# ATmega328P_design.net
KiCad netlist of a schematic drawn in Altium Designer
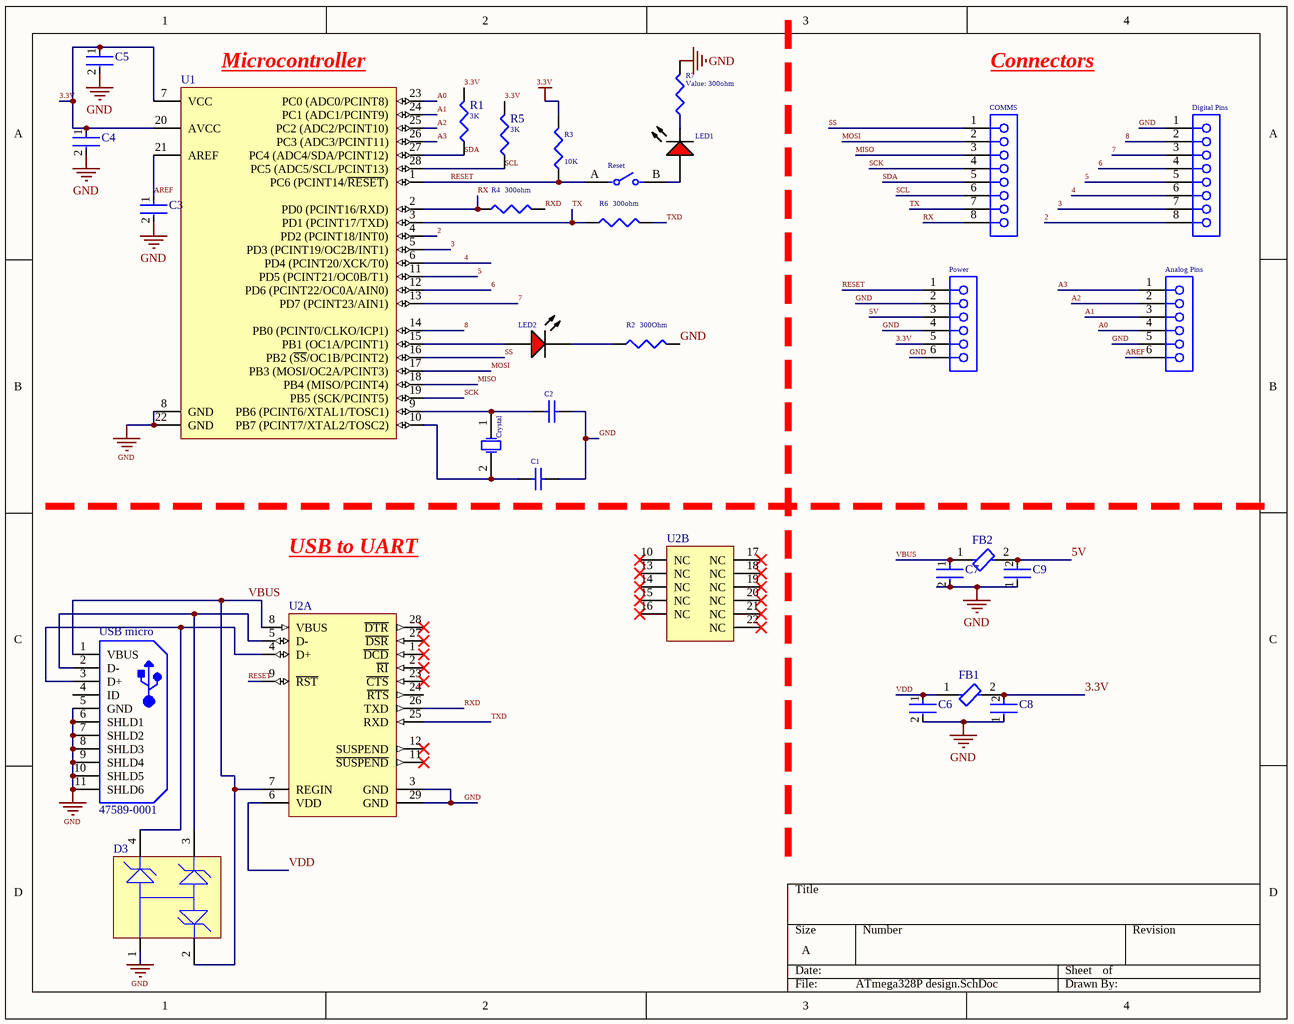
[diagram p0: ATmega328P design.SchDoc]

(export (version "E")
  (design (tool "Eeschema 10.0.6"))
  (components
    (comp (ref "Analog Pins")
      (value "SSW-106-02-G-S")
      (footprint "SMTC-SSW-106-02-X-S")
      (description "SQ Post Socket, Through-hole, Vertical, -55 to 125 degC, 2.54mm Pitch, 6-Pin, Female, RoHS")
      (fields (field (name "MANUFACTURER") "Samtec"))
      (libsource (lib "Altium Content Vault") (part "SMTC-SSW-106-02-X-S-X"))
    )
    (comp (ref "C1")
      (value "22pF")
      (footprint "CAPC1608X90X35LL15T15")
      (fields
        (field (name "MANUFACTURER") "AVX Interconnect / Elco")
        (field (name "PART NUMBER") "06031A220KAT2A")
      )
      (libsource (lib "Altium Content Vault") (part "CAP"))
    )
    (comp (ref "C2")
      (value "22pf")
      (footprint "CAPC1608X90X35LL15T15")
      (fields
        (field (name "MANUFACTURER") "AVX Interconnect / Elco")
        (field (name "PART NUMBER") "06031A220KAT2A")
      )
      (libsource (lib "Altium Content Vault") (part "CAP"))
    )
    (comp (ref "C3")
      (value "GRM188R60J106ME47D")
      (footprint "FP-GRM188-0_1-e0_2_0_55-IPC_A")
      (description "Chip Multilayer Ceramic Capacitors for General Purpose, 0603, 0.1uF, X5R, 15%, 20%, 6.3V")
      (fields (field (name "VOLTAGE") "6.3V") (field (name "TOLERANCE") "20%"))
      (libsource (lib "Altium Content Vault") (part "02cd4be3c70576c341d710602a673aa"))
    )
    (comp (ref "C4")
      (value "GRM188R61A226ME15D")
      (footprint "FP-GRM188-0_2-IPC_C")
      (description "Chip Multilayer Ceramic Capacitors for General Purpose, 0603, 22uF, X5R, 15%, 20%, 10V")
      (fields (field (name "TOLERANCE") "20%"))
      (libsource (lib "Altium Content Vault") (part "11868f565c42a9108669ba33697ecf6"))
    )
    (comp (ref "C5")
      (value "GRM188R61A226ME15D")
      (footprint "FP-GRM188-0_2-IPC_C")
      (description "Chip Multilayer Ceramic Capacitors for General Purpose, 0603, 22uF, X5R, 15%, 20%, 10V")
      (fields (field (name "TOLERANCE") "20%"))
      (libsource (lib "Altium Content Vault") (part "11868f565c42a9108669ba33697ecf6"))
    )
    (comp (ref "C6")
      (value "GRM188R6YA106MA73D")
      (footprint "FP-GRM188-0_2-IPC_C")
      (description "Chip Multilayer Ceramic Capacitors for General Purpose, 0603, 10uF, X5R, 15%, 20%, 35V")
      (fields (field (name "TOLERANCE") "20%"))
      (libsource (lib "Altium Content Vault") (part "11868f565c42a9108669ba33697ecf6"))
    )
    (comp (ref "C7")
      (value "GRM188R6YA106MA73D")
      (footprint "FP-GRM188-0_2-IPC_C")
      (description "Chip Multilayer Ceramic Capacitors for General Purpose, 0603, 10uF, X5R, 15%, 20%, 35V")
      (fields (field (name "TOLERANCE") "20%"))
      (libsource (lib "Altium Content Vault") (part "11868f565c42a9108669ba33697ecf6"))
    )
    (comp (ref "C8")
      (value "GRM188R60J105KA01D")
      (footprint "FP-GRM188-0_1-MFG")
      (description "CAP CER 1UF 6.3V X5R 0603")
      (fields (field (name "TOLERANCE") "10%") (field (name "VOLTAGE") "6.3V"))
      (libsource (lib "Altium Content Vault") (part "236180d848d6139a670b325ea6854c9"))
    )
    (comp (ref "C9")
      (value "GRM188R60J105KA01D")
      (footprint "FP-GRM188-0_1-MFG")
      (description "CAP CER 1UF 6.3V X5R 0603")
      (fields (field (name "TOLERANCE") "10%") (field (name "VOLTAGE") "6.3V"))
      (libsource (lib "Altium Content Vault") (part "236180d848d6139a670b325ea6854c9"))
    )
    (comp (ref "COMMS")
      (value "SSQ-108-01-F-S")
      (footprint "SMTC-SSQ-108-01-X-S")
      (description "SQ Post Socket, Through-hole, Vertical, -55 to 125 degC, 2.54 mm Pitch, 8-Pin, Female, RoHS")
      (fields (field (name "MANUFACTURER") "Samtec"))
      (libsource (lib "Altium Content Vault") (part "SMTC-SSQ-108-X-X-S-X"))
    )
    (comp (ref "Crystal")
      (value "FOXSDLF/160-20")
      (footprint "FOX-FOXSDLF160-20_V")
      (libsource (lib "Altium Content Vault") (part "XTAL_1-2-2"))
    )
    (comp (ref "D3")
      (value "SP0503BAHTG")
      (footprint "LFUS-SOT143-4_V")
      (description "TVS Diode Array, 30 pF, 30 KV, -40 to 85 degC, 4-Pin SOT143, RoHS, Tape and Reel")
      (fields (field (name "MANUFACTURER") "Littelfuse"))
      (libsource (lib "Altium Content Vault") (part "LFUS-SP0503BAHTG-SOT143-4"))
    )
    (comp (ref "Digital Pins")
      (value "SSQ-108-01-F-S")
      (footprint "SMTC-SSQ-108-01-X-S")
      (description "SQ Post Socket, Through-hole, Vertical, -55 to 125 degC, 2.54 mm Pitch, 8-Pin, Female, RoHS")
      (fields (field (name "MANUFACTURER") "Samtec"))
      (libsource (lib "Altium Content Vault") (part "SMTC-SSQ-108-X-X-S-X"))
    )
    (comp (ref "FB1")
      (value "BLM18PG181SN1D")
      (footprint "FP-BLM18-0_15-t0_8-IPC_B")
      (description "Chip Ferrite Bead, 0603, 180Ω @ 100MHz, 0.09Ω, 25%, 1.5A")
      (fields (field (name "TOLERANCE") "25%"))
      (libsource (lib "Altium Content Vault") (part "5f30dd21d616792df468990f7003faa"))
    )
    (comp (ref "FB2")
      (value "BLM18PG181SN1D")
      (footprint "FP-BLM18-0_15-t0_8-IPC_B")
      (description "Chip Ferrite Bead, 0603, 180Ω @ 100MHz, 0.09Ω, 25%, 1.5A")
      (fields (field (name "TOLERANCE") "25%"))
      (libsource (lib "Altium Content Vault") (part "5f30dd21d616792df468990f7003faa"))
    )
    (comp (ref "LED1")
      (value "TLMS1100-GS08")
      (footprint "VISH-TLMX1100_V")
      (description "LED, RED, 2.1 V, -40 to 100 degC, 2-Pin SMD (0603), RoHS, Tape and Reel")
      (fields (field (name "TOLERANCE") "5%"))
      (libsource (lib "Altium Content Vault") (part "LED-RED-AK-2"))
    )
    (comp (ref "LED2")
      (value "TLMS1100-GS08")
      (footprint "VISH-TLMX1100_V")
      (description "LED, RED, 2.1 V, -40 to 100 degC, 2-Pin SMD (0603), RoHS, Tape and Reel")
      (fields (field (name "TOLERANCE") "5%"))
      (libsource (lib "Altium Content Vault") (part "LED-RED-AK-2"))
    )
    (comp (ref "Power")
      (value "SSW-106-02-G-S")
      (footprint "SMTC-SSW-106-02-X-S")
      (description "SQ Post Socket, Through-hole, Vertical, -55 to 125 degC, 2.54mm Pitch, 6-Pin, Female, RoHS")
      (fields (field (name "MANUFACTURER") "Samtec"))
      (libsource (lib "Altium Content Vault") (part "SMTC-SSW-106-02-X-S-X"))
    )
    (comp (ref "R1")
      (value "3K")
      (footprint "J1-0603")
      (description "Resistor")
      (fields (field (name "Comment") "Res3") (field (name "PUBLISHER") "Altium Limited"))
      (libsource (lib "Miscellaneous Devices") (part "Res3"))
    )
    (comp (ref "R2")
      (value "300Ohm")
      (footprint "J1-0603")
      (description "Resistor")
      (fields (field (name "PUBLISHER") "Altium Limited"))
      (libsource (lib "Miscellaneous Devices") (part "Res3"))
    )
    (comp (ref "R3")
      (value "10K")
      (footprint "J1-0603")
      (description "Resistor")
      (fields (field (name "Comment") "0603") (field (name "PUBLISHER") "Altium Limited"))
      (libsource (lib "Miscellaneous Devices") (part "Res3"))
    )
    (comp (ref "R4")
      (value "300ohm")
      (footprint "J1-0603")
      (description "Resistor")
      (fields (field (name "Comment") "Res3") (field (name "PUBLISHER") "Altium Limited"))
      (libsource (lib "Miscellaneous Devices") (part "Res3"))
    )
    (comp (ref "R5")
      (value "3K")
      (footprint "J1-0603")
      (description "Resistor")
      (fields (field (name "Comment") "Res3") (field (name "PUBLISHER") "Altium Limited"))
      (libsource (lib "Miscellaneous Devices") (part "Res3"))
    )
    (comp (ref "R6")
      (value "300ohm")
      (footprint "J1-0603")
      (description "Resistor")
      (fields (field (name "Comment") "Res3") (field (name "PUBLISHER") "Altium Limited"))
      (libsource (lib "Miscellaneous Devices") (part "Res3"))
    )
    (comp (ref "R7")
      (value "300ohm")
      (footprint "J1-0603")
      (description "Resistor")
      (fields (field (name "PUBLISHER") "Altium Limited"))
      (libsource (lib "Miscellaneous Devices") (part "Res3"))
    )
    (comp (ref "Reset")
      (value "EVQ-21405R")
      (footprint "FP-EVQ-21405R-MFG")
      (description "EVQ-21405R Switch Tactile N.O. SPST Round Button PC Pins 0.02A 15VDC 1.3N Thru-Hole Radial T/R")
      (libsource (lib "Altium Content Vault") (part "2b0b2b19372efd94fa7681498149756"))
    )
    (comp (ref "U1")
      (value "ATmega328P-PU")
      (footprint "28P3")
      (libsource (lib "Altium Content Vault") (part "MC-8B-ATM48-IL28"))
    )
    (comp (ref "U2")
      (value "CP2102-GM")
      (footprint "SLAB-QFN-28-3125x3125TP_N")
      (description "Single-Chip USB to UART Bridge, 1024 Bytes EEPROM, -40 to 85 degC, 28-pin QFN, Tube")
      (fields (field (name "MANUFACTURER") "Silicon Labs"))
      (libsource (lib "Altium Content Vault") (part "SLAB-CP210X-QFN-28-29"))
    )
    (comp (ref "USB micro")
      (value "47589-0001")
      (footprint "MOLX-47589-0001_V")
      (description "Right Angle Female Type AB Micro USB Connector, 30 V, 1.8 A, -30 to 85 degC, RoHS, Tape and Reel")
      (fields (field (name "MANUFACTURER") "Molex"))
      (libsource (lib "Altium Content Vault") (part "USB-5-6SHLD"))
    )
  )
  (nets
    (net (code "1") (name "/2") (class "Default")
      (node (ref "Digital Pins") (pin "8") (pinfunction "8_8") (pintype "passive"))
      (node (ref "U1") (pin "4") (pinfunction "PD2_(PCINT18/INT0)_4") (pintype "bidirectional"))
    )
    (net (code "2") (name "/3") (class "Default")
      (node (ref "Digital Pins") (pin "7") (pinfunction "7_7") (pintype "passive"))
      (node (ref "U1") (pin "5") (pinfunction "PD3_(PCINT19/OC2B/INT1)_5") (pintype "bidirectional"))
    )
    (net (code "3") (name "/4") (class "Default")
      (node (ref "Digital Pins") (pin "6") (pinfunction "6_6") (pintype "passive"))
      (node (ref "U1") (pin "6") (pinfunction "PD4_(PCINT20/XCK/T0)_6") (pintype "bidirectional"))
    )
    (net (code "4") (name "/5") (class "Default")
      (node (ref "Digital Pins") (pin "5") (pinfunction "5_5") (pintype "passive"))
      (node (ref "U1") (pin "11") (pinfunction "PD5_(PCINT21/OC0B/T1)_11") (pintype "bidirectional"))
    )
    (net (code "5") (name "/5V") (class "Default")
      (node (ref "C9") (pin "2") (pinfunction "2_2") (pintype "passive"))
      (node (ref "FB2") (pin "2") (pinfunction "2_2") (pintype "passive"))
      (node (ref "Power") (pin "3") (pinfunction "3_3") (pintype "passive"))
    )
    (net (code "6") (name "/6") (class "Default")
      (node (ref "Digital Pins") (pin "4") (pinfunction "4_4") (pintype "passive"))
      (node (ref "U1") (pin "12") (pinfunction "PD6_(PCINT22/OC0A/AIN0)_12") (pintype "bidirectional"))
    )
    (net (code "7") (name "/7") (class "Default")
      (node (ref "Digital Pins") (pin "3") (pinfunction "3_3") (pintype "passive"))
      (node (ref "U1") (pin "13") (pinfunction "PD7_(PCINT23/AIN1)_13") (pintype "bidirectional"))
    )
    (net (code "8") (name "/8") (class "Default")
      (node (ref "Digital Pins") (pin "2") (pinfunction "2_2") (pintype "passive"))
      (node (ref "U1") (pin "14") (pinfunction "PB0_(PCINT0/CLKO/ICP1)_14") (pintype "bidirectional"))
    )
    (net (code "9") (name "/A0") (class "Default")
      (node (ref "Analog Pins") (pin "4") (pinfunction "4_4") (pintype "passive"))
      (node (ref "U1") (pin "23") (pinfunction "PC0_(ADC0/PCINT8)_23") (pintype "bidirectional"))
    )
    (net (code "10") (name "/A1") (class "Default")
      (node (ref "Analog Pins") (pin "3") (pinfunction "3_3") (pintype "passive"))
      (node (ref "U1") (pin "24") (pinfunction "PC1_(ADC1/PCINT9)_24") (pintype "bidirectional"))
    )
    (net (code "11") (name "/A2") (class "Default")
      (node (ref "Analog Pins") (pin "2") (pinfunction "2_2") (pintype "passive"))
      (node (ref "U1") (pin "25") (pinfunction "PC2_(ADC2/PCINT10)_25") (pintype "bidirectional"))
    )
    (net (code "12") (name "/A3") (class "Default")
      (node (ref "Analog Pins") (pin "1") (pinfunction "1_1") (pintype "passive"))
      (node (ref "U1") (pin "26") (pinfunction "PC3_(ADC3/PCINT11)_26") (pintype "bidirectional"))
    )
    (net (code "13") (name "/AREF") (class "Default")
      (node (ref "Analog Pins") (pin "6") (pinfunction "6_6") (pintype "passive"))
      (node (ref "C3") (pin "1") (pinfunction "1_1") (pintype "passive"))
      (node (ref "U1") (pin "21") (pinfunction "AREF_21") (pintype "power_in"))
    )
    (net (code "14") (name "/MISO") (class "Default")
      (node (ref "COMMS") (pin "3") (pinfunction "3_3") (pintype "passive"))
      (node (ref "U1") (pin "18") (pinfunction "PB4_(MISO/PCINT4)_18") (pintype "bidirectional"))
    )
    (net (code "15") (name "/MOSI") (class "Default")
      (node (ref "COMMS") (pin "2") (pinfunction "2_2") (pintype "passive"))
      (node (ref "U1") (pin "17") (pinfunction "PB3_(MOSI/OC2A/PCINT3)_17") (pintype "bidirectional"))
    )
    (net (code "16") (name "/RESET") (class "Default")
      (node (ref "Power") (pin "1") (pinfunction "1_1") (pintype "passive"))
      (node (ref "R3") (pin "1") (pinfunction "1_1") (pintype "passive"))
      (node (ref "Reset") (pin "A") (pinfunction "A_A") (pintype "passive"))
      (node (ref "U1") (pin "1") (pinfunction "PC6_(PCINT14/~{RESET})_1") (pintype "bidirectional"))
      (node (ref "U2") (pin "9") (pinfunction "~{RST}_9") (pintype "bidirectional"))
    )
    (net (code "17") (name "/RX") (class "Default")
      (node (ref "COMMS") (pin "8") (pinfunction "8_8") (pintype "passive"))
      (node (ref "R4") (pin "1") (pinfunction "1_1") (pintype "passive"))
      (node (ref "U1") (pin "2") (pinfunction "PD0_(PCINT16/RXD)_2") (pintype "bidirectional"))
    )
    (net (code "18") (name "/RXD") (class "Default")
      (node (ref "R4") (pin "2") (pinfunction "2_2") (pintype "passive"))
      (node (ref "U2") (pin "26") (pinfunction "TXD_26") (pintype "output"))
    )
    (net (code "19") (name "/SCK") (class "Default")
      (node (ref "COMMS") (pin "4") (pinfunction "4_4") (pintype "passive"))
      (node (ref "U1") (pin "19") (pinfunction "PB5_(SCK/PCINT5)_19") (pintype "bidirectional"))
    )
    (net (code "20") (name "/SCL") (class "Default")
      (node (ref "COMMS") (pin "6") (pinfunction "6_6") (pintype "passive"))
      (node (ref "R5") (pin "1") (pinfunction "1_1") (pintype "passive"))
      (node (ref "U1") (pin "28") (pinfunction "PC5_(ADC5/SCL/PCINT13)_28") (pintype "bidirectional"))
    )
    (net (code "21") (name "/SDA") (class "Default")
      (node (ref "COMMS") (pin "5") (pinfunction "5_5") (pintype "passive"))
      (node (ref "R1") (pin "1") (pinfunction "1_1") (pintype "passive"))
      (node (ref "U1") (pin "27") (pinfunction "PC4_(ADC4/SDA/PCINT12)_27") (pintype "bidirectional"))
    )
    (net (code "22") (name "/SS") (class "Default")
      (node (ref "COMMS") (pin "1") (pinfunction "1_1") (pintype "passive"))
      (node (ref "U1") (pin "16") (pinfunction "PB2_(~{SS}/OC1B/PCINT2)_16") (pintype "bidirectional"))
    )
    (net (code "23") (name "/TX") (class "Default")
      (node (ref "COMMS") (pin "7") (pinfunction "7_7") (pintype "passive"))
      (node (ref "R6") (pin "1") (pinfunction "1_1") (pintype "passive"))
      (node (ref "U1") (pin "3") (pinfunction "PD1_(PCINT17/TXD)_3") (pintype "bidirectional"))
    )
    (net (code "24") (name "/TXD") (class "Default")
      (node (ref "R6") (pin "2") (pinfunction "2_2") (pintype "passive"))
      (node (ref "U2") (pin "25") (pinfunction "RXD_25") (pintype "input"))
    )
    (net (code "25") (name "/VBUS") (class "Default")
      (node (ref "C7") (pin "1") (pinfunction "1_1") (pintype "passive"))
      (node (ref "D3") (pin "2") (pinfunction "2_2") (pintype "passive"))
      (node (ref "FB2") (pin "1") (pinfunction "1_1") (pintype "passive"))
      (node (ref "U2") (pin "7") (pinfunction "REGIN_7") (pintype "power_in"))
      (node (ref "U2") (pin "8") (pinfunction "VBUS_8") (pintype "input"))
      (node (ref "USB micro") (pin "1") (pinfunction "VBUS_1") (pintype "passive"))
    )
    (net (code "26") (name "/VDD") (class "Default")
      (node (ref "C6") (pin "1") (pinfunction "1_1") (pintype "passive"))
      (node (ref "FB1") (pin "1") (pinfunction "1_1") (pintype "passive"))
      (node (ref "U2") (pin "6") (pinfunction "VDD_6") (pintype "power_in"))
    )
    (net (code "27") (name "3.3V") (class "Default")
      (node (ref "C4") (pin "1") (pinfunction "1_1") (pintype "passive"))
      (node (ref "C5") (pin "1") (pinfunction "1_1") (pintype "passive"))
      (node (ref "C8") (pin "2") (pinfunction "2_2") (pintype "passive"))
      (node (ref "FB1") (pin "2") (pinfunction "2_2") (pintype "passive"))
      (node (ref "Power") (pin "5") (pinfunction "5_5") (pintype "passive"))
      (node (ref "R1") (pin "2") (pinfunction "2_2") (pintype "passive"))
      (node (ref "R3") (pin "2") (pinfunction "2_2") (pintype "passive"))
      (node (ref "R5") (pin "2") (pinfunction "2_2") (pintype "passive"))
      (node (ref "U1") (pin "20") (pinfunction "AVCC_20") (pintype "power_in"))
      (node (ref "U1") (pin "7") (pinfunction "VCC_7") (pintype "power_in"))
    )
    (net (code "28") (name "GND") (class "Default")
      (node (ref "Analog Pins") (pin "5") (pinfunction "5_5") (pintype "passive"))
      (node (ref "C1") (pin "1") (pinfunction "1_1") (pintype "passive"))
      (node (ref "C2") (pin "1") (pinfunction "1_1") (pintype "passive"))
      (node (ref "C3") (pin "2") (pinfunction "2_2") (pintype "passive"))
      (node (ref "C4") (pin "2") (pinfunction "2_2") (pintype "passive"))
      (node (ref "C5") (pin "2") (pinfunction "2_2") (pintype "passive"))
      (node (ref "C6") (pin "2") (pinfunction "2_2") (pintype "passive"))
      (node (ref "C7") (pin "2") (pinfunction "2_2") (pintype "passive"))
      (node (ref "C8") (pin "1") (pinfunction "1_1") (pintype "passive"))
      (node (ref "C9") (pin "1") (pinfunction "1_1") (pintype "passive"))
      (node (ref "D3") (pin "1") (pinfunction "1_1") (pintype "passive"))
      (node (ref "Digital Pins") (pin "1") (pinfunction "1_1") (pintype "passive"))
      (node (ref "Power") (pin "2") (pinfunction "2_2") (pintype "passive"))
      (node (ref "Power") (pin "4") (pinfunction "4_4") (pintype "passive"))
      (node (ref "Power") (pin "6") (pinfunction "6_6") (pintype "passive"))
      (node (ref "R2") (pin "2") (pinfunction "2_2") (pintype "passive"))
      (node (ref "R7") (pin "2") (pinfunction "2_2") (pintype "passive"))
      (node (ref "U1") (pin "22") (pinfunction "GND_22") (pintype "power_in"))
      (node (ref "U1") (pin "8") (pinfunction "GND_8") (pintype "power_in"))
      (node (ref "U2") (pin "29") (pinfunction "GND_29") (pintype "power_in"))
      (node (ref "U2") (pin "3") (pinfunction "GND_3") (pintype "power_in"))
      (node (ref "USB micro") (pin "10") (pinfunction "SHLD5_10") (pintype "passive"))
      (node (ref "USB micro") (pin "11") (pinfunction "SHLD6_11") (pintype "passive"))
      (node (ref "USB micro") (pin "5") (pinfunction "GND_5") (pintype "passive"))
      (node (ref "USB micro") (pin "6") (pinfunction "SHLD1_6") (pintype "passive"))
      (node (ref "USB micro") (pin "7") (pinfunction "SHLD2_7") (pintype "passive"))
      (node (ref "USB micro") (pin "8") (pinfunction "SHLD3_8") (pintype "passive"))
      (node (ref "USB micro") (pin "9") (pinfunction "SHLD4_9") (pintype "passive"))
    )
    (net (code "29") (name "Net-(Crystal-X1)") (class "Default")
      (node (ref "C2") (pin "2") (pinfunction "2_2") (pintype "passive"))
      (node (ref "Crystal") (pin "1") (pinfunction "X1_1") (pintype "passive"))
      (node (ref "U1") (pin "9") (pinfunction "PB6_(PCINT6/XTAL1/TOSC1)_9") (pintype "bidirectional"))
    )
    (net (code "30") (name "Net-(Crystal-X2)") (class "Default")
      (node (ref "C1") (pin "2") (pinfunction "2_2") (pintype "passive"))
      (node (ref "Crystal") (pin "2") (pinfunction "X2_2") (pintype "passive"))
      (node (ref "U1") (pin "10") (pinfunction "PB7_(PCINT7/XTAL2/TOSC2)_10") (pintype "bidirectional"))
    )
    (net (code "31") (name "Net-(LED1-A)") (class "Default")
      (node (ref "LED1") (pin "1") (pinfunction "A_1") (pintype "passive"))
      (node (ref "Reset") (pin "B") (pinfunction "B_B") (pintype "passive"))
    )
    (net (code "32") (name "Net-(LED1-K)") (class "Default")
      (node (ref "LED1") (pin "2") (pinfunction "K_2") (pintype "passive"))
      (node (ref "R7") (pin "1") (pinfunction "1_1") (pintype "passive"))
    )
    (net (code "33") (name "Net-(LED2-A)") (class "Default")
      (node (ref "LED2") (pin "1") (pinfunction "A_1") (pintype "passive"))
      (node (ref "U1") (pin "15") (pinfunction "PB1_(OC1A/PCINT1)_15") (pintype "bidirectional"))
    )
    (net (code "34") (name "Net-(LED2-K)") (class "Default")
      (node (ref "LED2") (pin "2") (pinfunction "K_2") (pintype "passive"))
      (node (ref "R2") (pin "1") (pinfunction "1_1") (pintype "passive"))
    )
    (net (code "35") (name "Net-(U2A-D+)") (class "Default")
      (node (ref "D3") (pin "4") (pinfunction "4_4") (pintype "passive"))
      (node (ref "U2") (pin "4") (pinfunction "D+_4") (pintype "bidirectional"))
      (node (ref "USB micro") (pin "3") (pinfunction "D+_3") (pintype "passive"))
    )
    (net (code "36") (name "Net-(U2A-D-)") (class "Default")
      (node (ref "D3") (pin "3") (pinfunction "3_3") (pintype "passive"))
      (node (ref "U2") (pin "5") (pinfunction "D-_5") (pintype "bidirectional"))
      (node (ref "USB micro") (pin "2") (pinfunction "D-_2") (pintype "passive"))
    )
    (net (code "37") (name "unconnected-(U2A-SUSPEND-Pad12)") (class "Default")
      (node (ref "U2") (pin "12") (pinfunction "SUSPEND_12") (pintype "output+no_connect"))
    )
    (net (code "38") (name "unconnected-(U2A-~{CTS}-Pad23)") (class "Default")
      (node (ref "U2") (pin "23") (pinfunction "~{CTS}_23") (pintype "input+no_connect"))
    )
    (net (code "39") (name "unconnected-(U2A-~{DCD}-Pad1)") (class "Default")
      (node (ref "U2") (pin "1") (pinfunction "~{DCD}_1") (pintype "input+no_connect"))
    )
    (net (code "40") (name "unconnected-(U2A-~{DSR}-Pad27)") (class "Default")
      (node (ref "U2") (pin "27") (pinfunction "~{DSR}_27") (pintype "input+no_connect"))
    )
    (net (code "41") (name "unconnected-(U2A-~{DTR}-Pad28)") (class "Default")
      (node (ref "U2") (pin "28") (pinfunction "~{DTR}_28") (pintype "output+no_connect"))
    )
    (net (code "42") (name "unconnected-(U2A-~{RI}-Pad2)") (class "Default")
      (node (ref "U2") (pin "2") (pinfunction "~{RI}_2") (pintype "input+no_connect"))
    )
    (net (code "43") (name "unconnected-(U2A-~{RTS}-Pad24)") (class "Default")
      (node (ref "U2") (pin "24") (pinfunction "~{RTS}_24") (pintype "output"))
    )
    (net (code "44") (name "unconnected-(U2A-~{SUSPEND}-Pad11)") (class "Default")
      (node (ref "U2") (pin "11") (pinfunction "~{SUSPEND}_11") (pintype "output+no_connect"))
    )
    (net (code "45") (name "unconnected-(U2B-NC-Pad10)") (class "Default")
      (node (ref "U2") (pin "10") (pinfunction "NC_10") (pintype "passive+no_connect"))
    )
    (net (code "46") (name "unconnected-(U2B-NC-Pad13)") (class "Default")
      (node (ref "U2") (pin "13") (pinfunction "NC_13") (pintype "passive+no_connect"))
    )
    (net (code "47") (name "unconnected-(U2B-NC-Pad14)") (class "Default")
      (node (ref "U2") (pin "14") (pinfunction "NC_14") (pintype "passive+no_connect"))
    )
    (net (code "48") (name "unconnected-(U2B-NC-Pad15)") (class "Default")
      (node (ref "U2") (pin "15") (pinfunction "NC_15") (pintype "passive+no_connect"))
    )
    (net (code "49") (name "unconnected-(U2B-NC-Pad16)") (class "Default")
      (node (ref "U2") (pin "16") (pinfunction "NC_16") (pintype "passive+no_connect"))
    )
    (net (code "50") (name "unconnected-(U2B-NC-Pad17)") (class "Default")
      (node (ref "U2") (pin "17") (pinfunction "NC_17") (pintype "passive+no_connect"))
    )
    (net (code "51") (name "unconnected-(U2B-NC-Pad18)") (class "Default")
      (node (ref "U2") (pin "18") (pinfunction "NC_18") (pintype "passive+no_connect"))
    )
    (net (code "52") (name "unconnected-(U2B-NC-Pad19)") (class "Default")
      (node (ref "U2") (pin "19") (pinfunction "NC_19") (pintype "passive+no_connect"))
    )
    (net (code "53") (name "unconnected-(U2B-NC-Pad20)") (class "Default")
      (node (ref "U2") (pin "20") (pinfunction "NC_20") (pintype "passive+no_connect"))
    )
    (net (code "54") (name "unconnected-(U2B-NC-Pad21)") (class "Default")
      (node (ref "U2") (pin "21") (pinfunction "NC_21") (pintype "passive+no_connect"))
    )
    (net (code "55") (name "unconnected-(U2B-NC-Pad22)") (class "Default")
      (node (ref "U2") (pin "22") (pinfunction "NC_22") (pintype "passive+no_connect"))
    )
    (net (code "56") (name "unconnected-(USB micro-ID-Pad4)") (class "Default")
      (node (ref "USB micro") (pin "4") (pinfunction "ID_4") (pintype "passive"))
    )
  )
)
